# SCH.net
KiCad netlist of a schematic drawn in Altium Designer
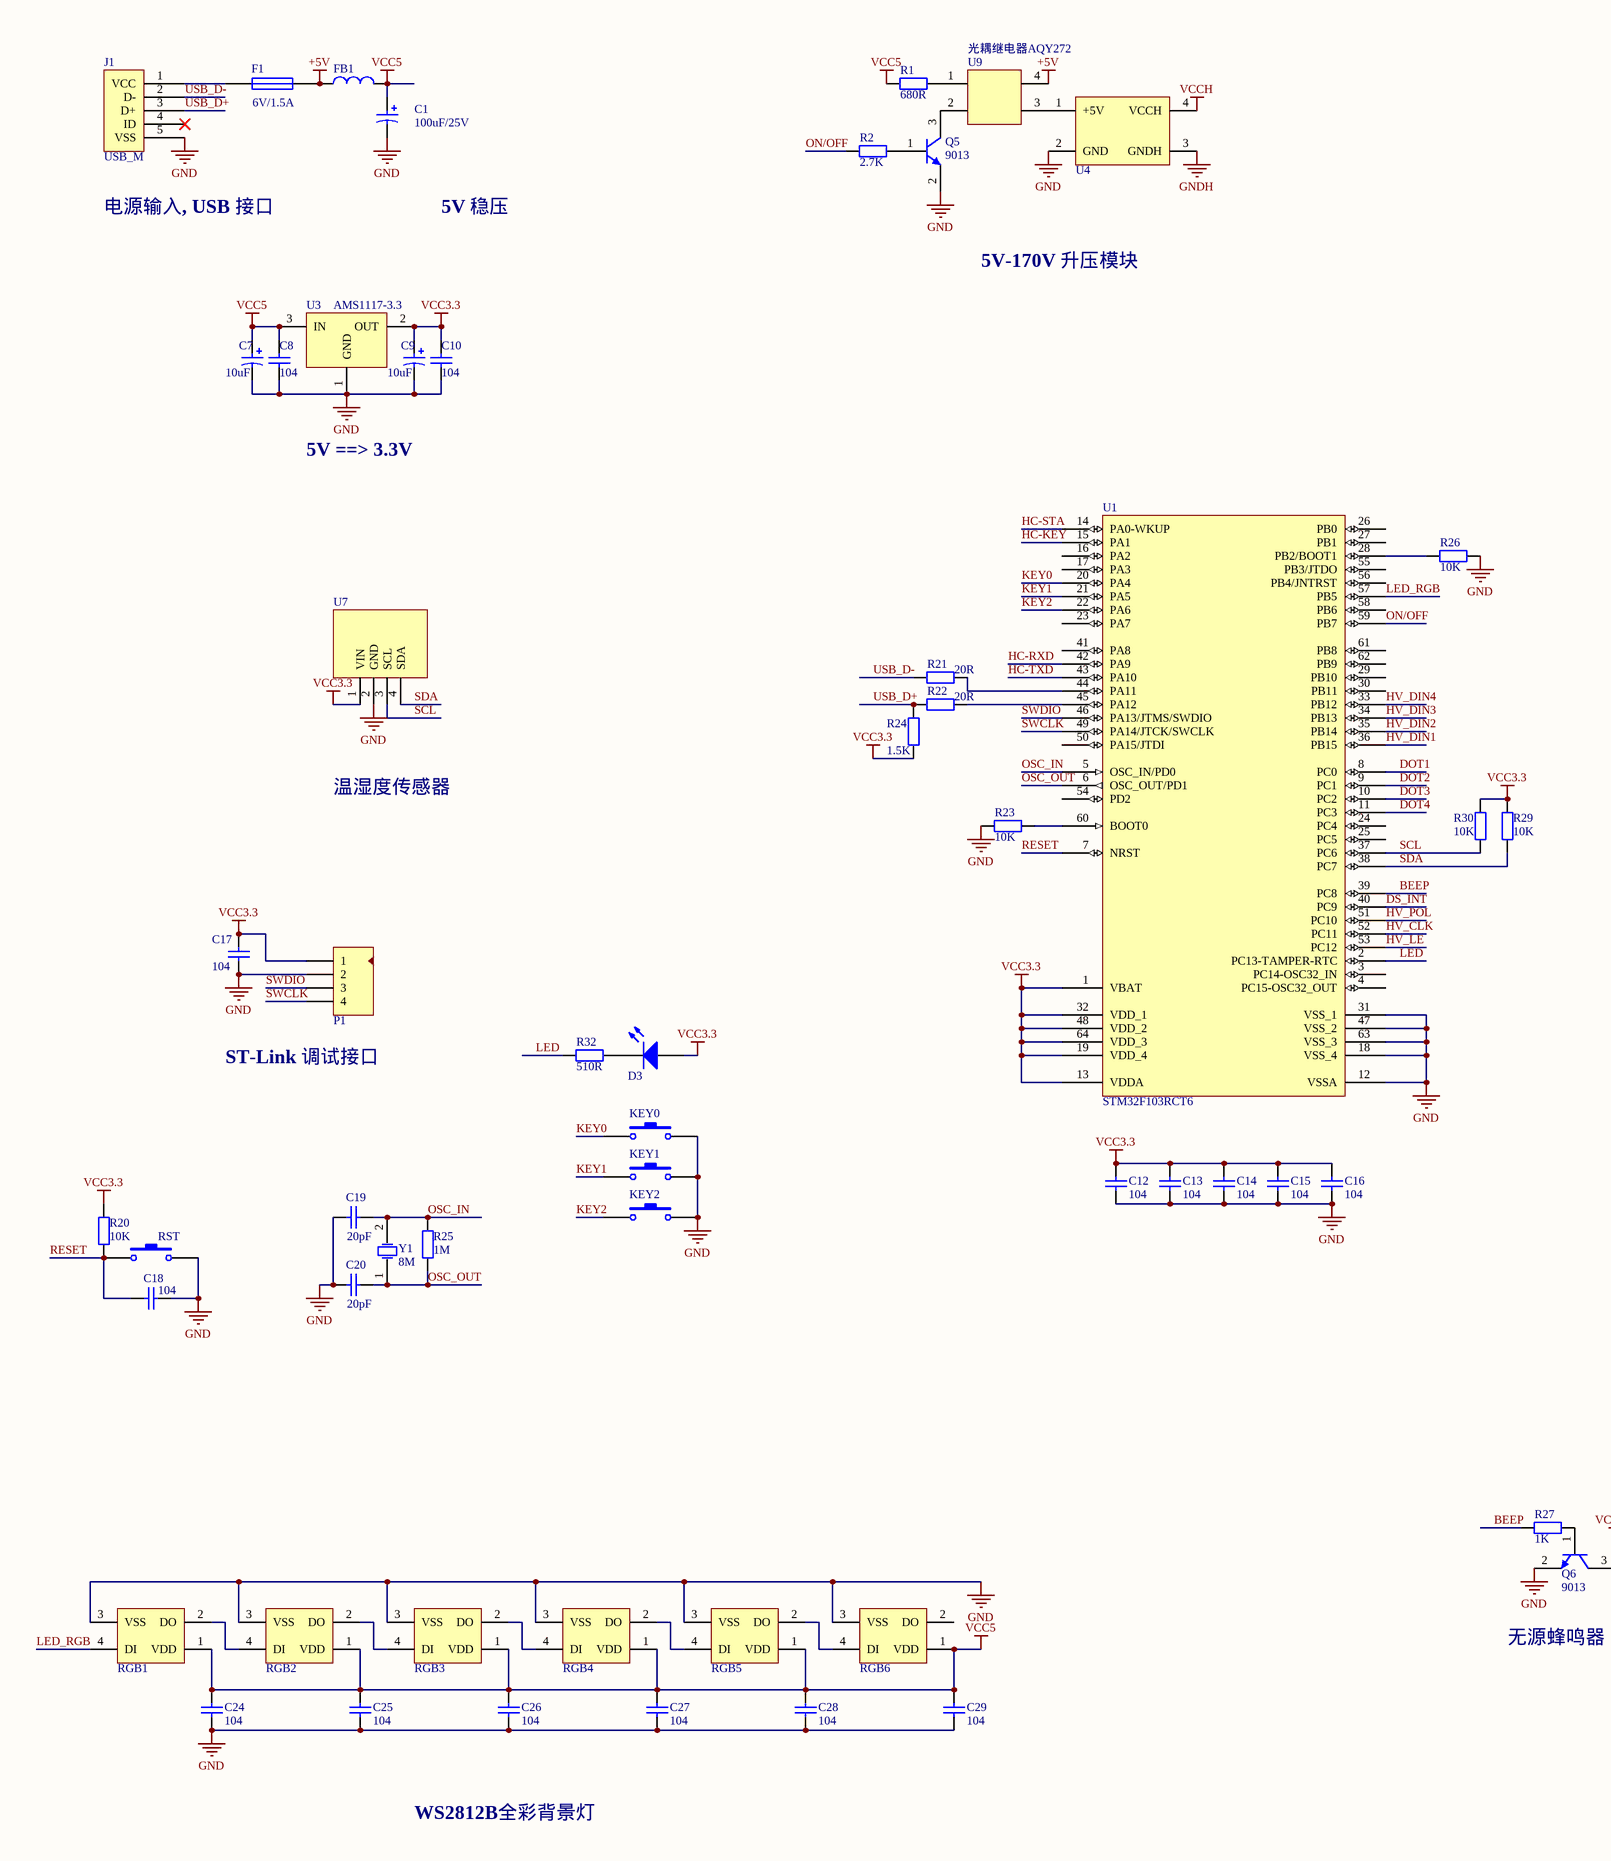
[diagram p0: SCH.SchDoc, left]
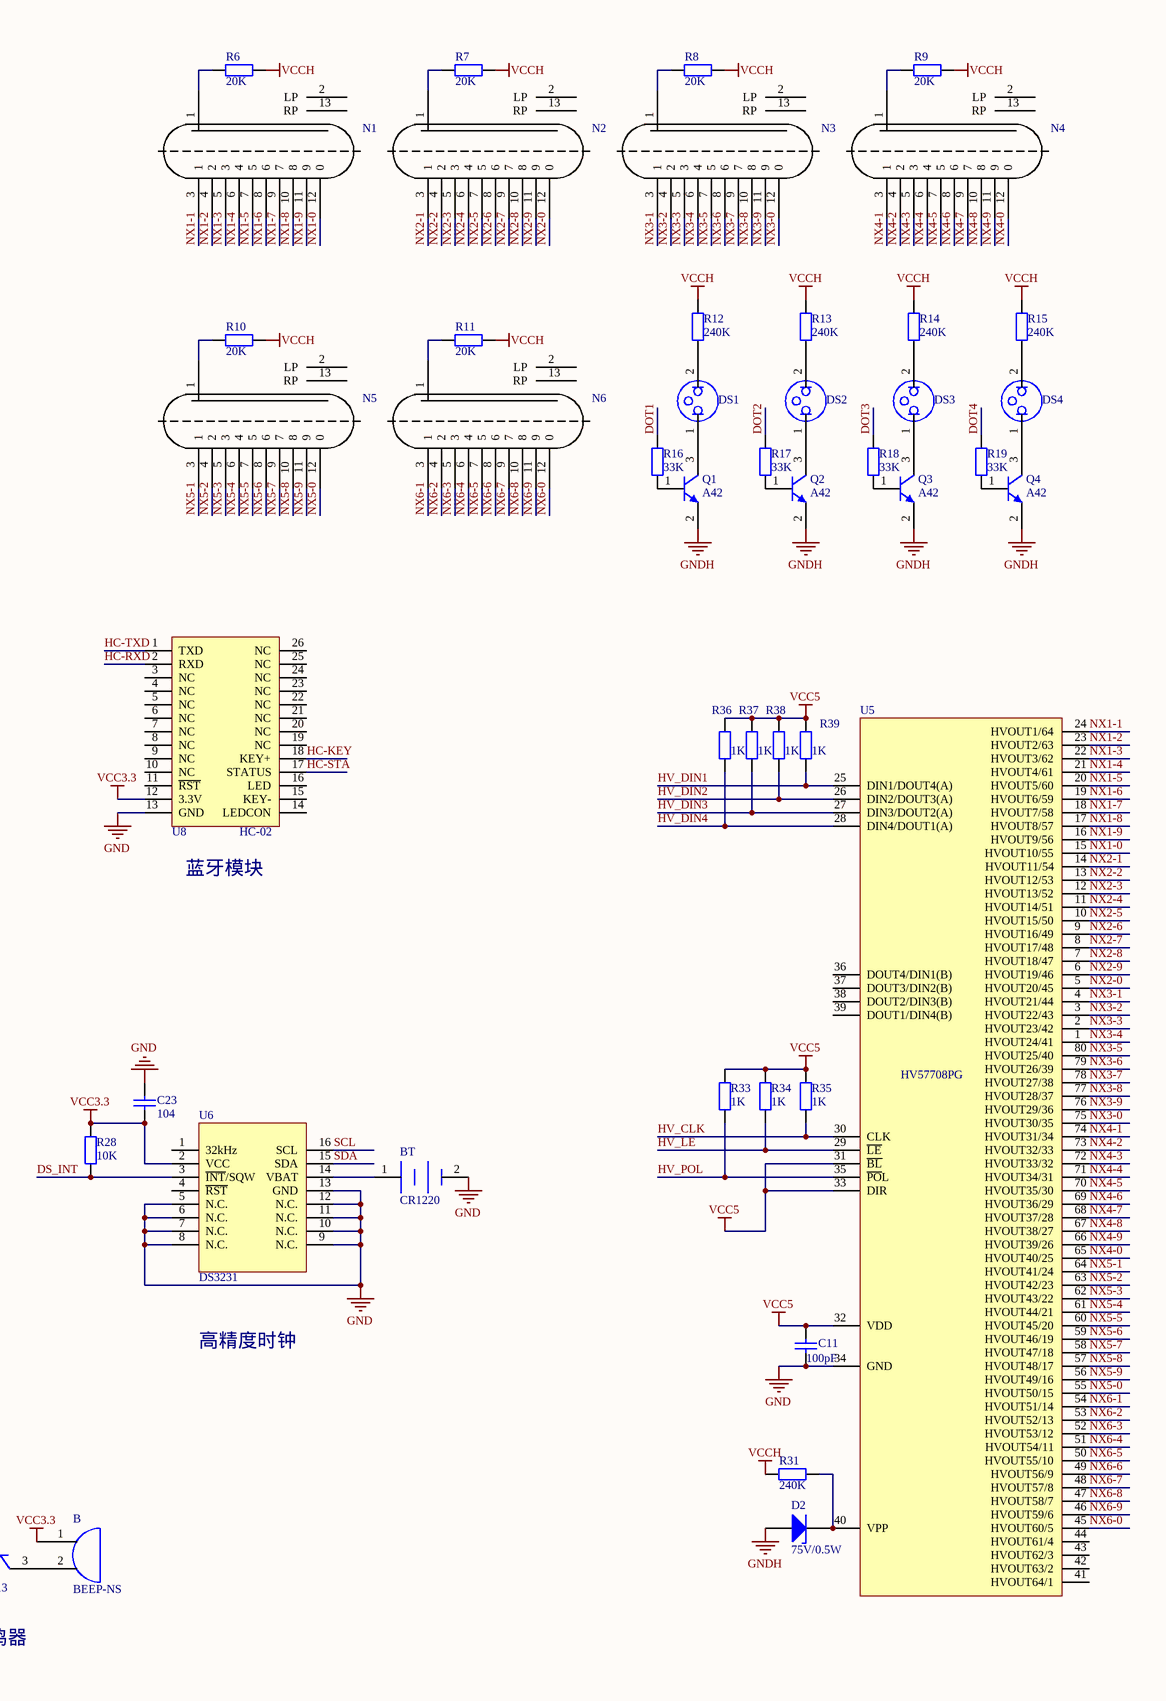
[diagram p1: SCH.SchDoc, right]

(export (version "E")
  (design (tool "Eeschema 10.0.6"))
  (components
    (comp (ref "B")
      (value "BEEP-NS")
      (footprint "BEEP-NS")
      (description "无源蜂鸣器")
      (libsource (lib "ChunLee") (part "BEEP-NS"))
    )
    (comp (ref "BT")
      (value "Battery")
      (footprint "CR1220")
      (fields (field (name "TYPE") "CR1220"))
      (libsource (lib "ChunLee") (part "Battery"))
    )
    (comp (ref "C1")
      (value "100uF/25V")
      (footprint "C-RB-SMD6.3x7.7")
      (description "贴片铝电解电容")
      (fields (field (name "Comment") "Cap-Pol-ES") (field (name "PUBLISHER") "Altium Limited"))
      (libsource (lib "ChunLee") (part "Cap-Pol-ES"))
    )
    (comp (ref "C7")
      (value "10uF")
      (footprint "C-1210")
      (description "钽电容")
      (fields (field (name "Comment") "Cap-Pol") (field (name "PUBLISHER") "Altium Limited"))
      (libsource (lib "ChunLee") (part "Cap-Pol-A"))
    )
    (comp (ref "C8")
      (value "104")
      (footprint "C-0805")
      (description "贴片瓷片电容")
      (fields (field (name "Comment") "Cap-S") (field (name "PUBLISHER") "Altium Limited"))
      (libsource (lib "ChunLee") (part "Cap-S"))
    )
    (comp (ref "C9")
      (value "10uF")
      (footprint "C-1210")
      (description "钽电容")
      (fields (field (name "Comment") "Cap-Pol") (field (name "PUBLISHER") "Altium Limited"))
      (libsource (lib "ChunLee") (part "Cap-Pol-A"))
    )
    (comp (ref "C10")
      (value "104")
      (footprint "C-0805")
      (description "贴片瓷片电容")
      (fields (field (name "Comment") "Cap-S") (field (name "PUBLISHER") "Altium Limited"))
      (libsource (lib "ChunLee") (part "Cap-S"))
    )
    (comp (ref "C11")
      (value "100pF")
      (footprint "C-0805")
      (description "贴片瓷片电容")
      (fields (field (name "Comment") "Cap-S") (field (name "PUBLISHER") "Altium Limited"))
      (libsource (lib "ChunLee") (part "Cap-S"))
    )
    (comp (ref "C12")
      (value "104")
      (footprint "C-0805")
      (description "贴片瓷片电容")
      (fields (field (name "Comment") "Cap-S") (field (name "PUBLISHER") "Altium Limited"))
      (libsource (lib "ChunLee") (part "Cap-S"))
    )
    (comp (ref "C13")
      (value "104")
      (footprint "C-0805")
      (description "贴片瓷片电容")
      (fields (field (name "Comment") "Cap-S") (field (name "PUBLISHER") "Altium Limited"))
      (libsource (lib "ChunLee") (part "Cap-S"))
    )
    (comp (ref "C14")
      (value "104")
      (footprint "C-0805")
      (description "贴片瓷片电容")
      (fields (field (name "Comment") "Cap-S") (field (name "PUBLISHER") "Altium Limited"))
      (libsource (lib "ChunLee") (part "Cap-S"))
    )
    (comp (ref "C15")
      (value "104")
      (footprint "C-0805")
      (description "贴片瓷片电容")
      (fields (field (name "Comment") "Cap-S") (field (name "PUBLISHER") "Altium Limited"))
      (libsource (lib "ChunLee") (part "Cap-S"))
    )
    (comp (ref "C16")
      (value "104")
      (footprint "C-0805")
      (description "贴片瓷片电容")
      (fields (field (name "Comment") "Cap-S") (field (name "PUBLISHER") "Altium Limited"))
      (libsource (lib "ChunLee") (part "Cap-S"))
    )
    (comp (ref "C17")
      (value "104")
      (footprint "C-0805")
      (description "贴片瓷片电容")
      (fields (field (name "Comment") "Cap-S") (field (name "PUBLISHER") "Altium Limited"))
      (libsource (lib "ChunLee") (part "Cap-S"))
    )
    (comp (ref "C18")
      (value "104")
      (footprint "C-0805")
      (description "贴片瓷片电容")
      (fields (field (name "Comment") "Cap-S") (field (name "PUBLISHER") "Altium Limited"))
      (libsource (lib "ChunLee") (part "Cap-S"))
    )
    (comp (ref "C19")
      (value "20pF")
      (footprint "C-0805")
      (description "贴片瓷片电容")
      (fields (field (name "Comment") "Cap-S") (field (name "PUBLISHER") "Altium Limited"))
      (libsource (lib "ChunLee") (part "Cap-S"))
    )
    (comp (ref "C20")
      (value "20pF")
      (footprint "C-0805")
      (description "贴片瓷片电容")
      (fields (field (name "Comment") "Cap-S") (field (name "PUBLISHER") "Altium Limited"))
      (libsource (lib "ChunLee") (part "Cap-S"))
    )
    (comp (ref "C23")
      (value "104")
      (footprint "C-0805")
      (description "贴片瓷片电容")
      (fields (field (name "Comment") "Cap-S") (field (name "PUBLISHER") "Altium Limited"))
      (libsource (lib "ChunLee") (part "Cap-S"))
    )
    (comp (ref "C24")
      (value "104")
      (footprint "C-0805")
      (description "贴片瓷片电容")
      (fields (field (name "Comment") "Cap-S") (field (name "PUBLISHER") "Altium Limited"))
      (libsource (lib "ChunLee") (part "Cap-S"))
    )
    (comp (ref "C25")
      (value "104")
      (footprint "C-0805")
      (description "贴片瓷片电容")
      (fields (field (name "Comment") "Cap-S") (field (name "PUBLISHER") "Altium Limited"))
      (libsource (lib "ChunLee") (part "Cap-S"))
    )
    (comp (ref "C26")
      (value "104")
      (footprint "C-0805")
      (description "贴片瓷片电容")
      (fields (field (name "Comment") "Cap-S") (field (name "PUBLISHER") "Altium Limited"))
      (libsource (lib "ChunLee") (part "Cap-S"))
    )
    (comp (ref "C27")
      (value "104")
      (footprint "C-0805")
      (description "贴片瓷片电容")
      (fields (field (name "Comment") "Cap-S") (field (name "PUBLISHER") "Altium Limited"))
      (libsource (lib "ChunLee") (part "Cap-S"))
    )
    (comp (ref "C28")
      (value "104")
      (footprint "C-0805")
      (description "贴片瓷片电容")
      (fields (field (name "Comment") "Cap-S") (field (name "PUBLISHER") "Altium Limited"))
      (libsource (lib "ChunLee") (part "Cap-S"))
    )
    (comp (ref "C29")
      (value "104")
      (footprint "C-0805")
      (description "贴片瓷片电容")
      (fields (field (name "Comment") "Cap-S") (field (name "PUBLISHER") "Altium Limited"))
      (libsource (lib "ChunLee") (part "Cap-S"))
    )
    (comp (ref "D2")
      (value "75V/0.5W")
      (footprint "D-ll34")
      (description "稳压二极管")
      (fields (field (name "Comment") "ZMM75") (field (name "PUBLISHER") "Altium Limited"))
      (libsource (lib "ChunLee") (part "Diode-Z"))
    )
    (comp (ref "D3")
      (value "LED0")
      (footprint "LED-0805")
      (description "发光二极管")
      (fields (field (name "PUBLISHER") "Altium Limited"))
      (libsource (lib "ChunLee") (part "LED0"))
    )
    (comp (ref "DS1")
      (value "Neon")
      (footprint "PIN2")
      (description "氖泡")
      (libsource (lib "ChunLee") (part "Neon_Lamp"))
    )
    (comp (ref "DS2")
      (value "Neon")
      (footprint "PIN2")
      (description "氖泡")
      (libsource (lib "ChunLee") (part "Neon_Lamp"))
    )
    (comp (ref "DS3")
      (value "Neon")
      (footprint "PIN2")
      (description "氖泡")
      (libsource (lib "ChunLee") (part "Neon_Lamp"))
    )
    (comp (ref "DS4")
      (value "Neon")
      (footprint "PIN2")
      (description "氖泡")
      (libsource (lib "ChunLee") (part "Neon_Lamp"))
    )
    (comp (ref "F1")
      (value "6V/1.5A")
      (footprint "1206")
      (description "保险丝")
      (fields (field (name "Comment") "Fuse1"))
      (libsource (lib "ChunLee") (part "Fuse1"))
    )
    (comp (ref "FB1")
      (value "Inductor")
      (footprint "0805-1")
      (description "磁珠")
      (fields (field (name "PUBLISHER") "Altium Limited"))
      (libsource (lib "ChunLee") (part "Inductor"))
    )
    (comp (ref "J1")
      (value "USB_M")
      (footprint "USB_MICRO")
      (description "Micro/Mini USB")
      (libsource (lib "HDR_ChunLee") (part "USB_M"))
    )
    (comp (ref "KEY0")
      (value "KEY")
      (footprint "SW_PB2_C1")
      (description "微动开关")
      (fields (field (name "PUBLISHER") "Altium Limited"))
      (libsource (lib "ChunLee") (part "SW-PB"))
    )
    (comp (ref "KEY1")
      (value "KEY")
      (footprint "SW_PB2_C1")
      (description "微动开关")
      (fields (field (name "PUBLISHER") "Altium Limited"))
      (libsource (lib "ChunLee") (part "SW-PB"))
    )
    (comp (ref "KEY2")
      (value "KEY")
      (footprint "SW_PB2_C1")
      (description "微动开关")
      (fields (field (name "PUBLISHER") "Altium Limited"))
      (libsource (lib "ChunLee") (part "SW-PB"))
    )
    (comp (ref "N1")
      (value "IN_14")
      (footprint "IN_14")
      (description "辉光管")
      (libsource (lib "ChunLee") (part "IN_14"))
    )
    (comp (ref "N2")
      (value "IN_14")
      (footprint "IN_14")
      (description "辉光管")
      (libsource (lib "ChunLee") (part "IN_14"))
    )
    (comp (ref "N3")
      (value "IN_14")
      (footprint "IN_14")
      (description "辉光管")
      (libsource (lib "ChunLee") (part "IN_14"))
    )
    (comp (ref "N4")
      (value "IN_14")
      (footprint "IN_14")
      (description "辉光管")
      (libsource (lib "ChunLee") (part "IN_14"))
    )
    (comp (ref "N5")
      (value "IN_14")
      (footprint "IN_14")
      (description "辉光管")
      (libsource (lib "ChunLee") (part "IN_14"))
    )
    (comp (ref "N6")
      (value "IN_14")
      (footprint "IN_14")
      (description "辉光管")
      (libsource (lib "ChunLee") (part "IN_14"))
    )
    (comp (ref "P1")
      (value "Header 4")
      (footprint "HDR4X1-2.54")
      (description "接插件")
      (fields (field (name "PUBLISHER") "Altium Limited"))
      (libsource (lib "HDR_ChunLee") (part "Header 4"))
    )
    (comp (ref "Q1")
      (value "A42")
      (footprint "SOT23-3")
      (description "贴片三极管")
      (fields (field (name "PUBLISHER") "Altium Limited"))
      (libsource (lib "ChunLee") (part "NPN1"))
    )
    (comp (ref "Q2")
      (value "A42")
      (footprint "SOT23-3")
      (description "贴片三极管")
      (fields (field (name "PUBLISHER") "Altium Limited"))
      (libsource (lib "ChunLee") (part "NPN1"))
    )
    (comp (ref "Q3")
      (value "A42")
      (footprint "SOT23-3")
      (description "贴片三极管")
      (fields (field (name "PUBLISHER") "Altium Limited"))
      (libsource (lib "ChunLee") (part "NPN1"))
    )
    (comp (ref "Q4")
      (value "A42")
      (footprint "SOT23-3")
      (description "贴片三极管")
      (fields (field (name "PUBLISHER") "Altium Limited"))
      (libsource (lib "ChunLee") (part "NPN1"))
    )
    (comp (ref "Q5")
      (value "9013")
      (footprint "SOT23-3")
      (description "贴片三极管")
      (fields (field (name "PUBLISHER") "Altium Limited"))
      (libsource (lib "ChunLee") (part "NPN1"))
    )
    (comp (ref "Q6")
      (value "9013")
      (footprint "SOT23-3")
      (description "贴片三极管")
      (fields (field (name "PUBLISHER") "Altium Limited"))
      (libsource (lib "ChunLee") (part "NPN1"))
    )
    (comp (ref "R1")
      (value "680R")
      (footprint "0805-1")
      (description "贴片电阻")
      (fields (field (name "Comment") "Res1") (field (name "PUBLISHER") "Altium Limited"))
      (libsource (lib "ChunLee") (part "Res1"))
    )
    (comp (ref "R2")
      (value "2.7K")
      (footprint "0805-1")
      (description "贴片电阻")
      (fields (field (name "Comment") "Res1") (field (name "PUBLISHER") "Altium Limited"))
      (libsource (lib "") (part "Res1_1"))
    )
    (comp (ref "R6")
      (value "20K")
      (footprint "0805-1")
      (description "贴片电阻")
      (fields (field (name "Comment") "Res1") (field (name "PUBLISHER") "Altium Limited"))
      (libsource (lib "ChunLee") (part "Res1"))
    )
    (comp (ref "R7")
      (value "20K")
      (footprint "0805-1")
      (description "贴片电阻")
      (fields (field (name "Comment") "Res1") (field (name "PUBLISHER") "Altium Limited"))
      (libsource (lib "ChunLee") (part "Res1"))
    )
    (comp (ref "R8")
      (value "20K")
      (footprint "0805-1")
      (description "贴片电阻")
      (fields (field (name "Comment") "Res1") (field (name "PUBLISHER") "Altium Limited"))
      (libsource (lib "ChunLee") (part "Res1"))
    )
    (comp (ref "R9")
      (value "20K")
      (footprint "0805-1")
      (description "贴片电阻")
      (fields (field (name "Comment") "Res1") (field (name "PUBLISHER") "Altium Limited"))
      (libsource (lib "ChunLee") (part "Res1"))
    )
    (comp (ref "R10")
      (value "20K")
      (footprint "0805-1")
      (description "贴片电阻")
      (fields (field (name "Comment") "Res1") (field (name "PUBLISHER") "Altium Limited"))
      (libsource (lib "ChunLee") (part "Res1"))
    )
    (comp (ref "R11")
      (value "20K")
      (footprint "0805-1")
      (description "贴片电阻")
      (fields (field (name "Comment") "Res1") (field (name "PUBLISHER") "Altium Limited"))
      (libsource (lib "ChunLee") (part "Res1"))
    )
    (comp (ref "R12")
      (value "240K")
      (footprint "0805-1")
      (description "贴片电阻")
      (fields (field (name "Comment") "Res1") (field (name "PUBLISHER") "Altium Limited"))
      (libsource (lib "") (part "Res1_2"))
    )
    (comp (ref "R13")
      (value "240K")
      (footprint "0805-1")
      (description "贴片电阻")
      (fields (field (name "Comment") "Res1") (field (name "PUBLISHER") "Altium Limited"))
      (libsource (lib "") (part "Res1_2"))
    )
    (comp (ref "R14")
      (value "240K")
      (footprint "0805-1")
      (description "贴片电阻")
      (fields (field (name "Comment") "Res1") (field (name "PUBLISHER") "Altium Limited"))
      (libsource (lib "") (part "Res1_3"))
    )
    (comp (ref "R15")
      (value "240K")
      (footprint "0805-1")
      (description "贴片电阻")
      (fields (field (name "Comment") "Res1") (field (name "PUBLISHER") "Altium Limited"))
      (libsource (lib "") (part "Res1_2"))
    )
    (comp (ref "R16")
      (value "33K")
      (footprint "0805-1")
      (description "贴片电阻")
      (fields (field (name "Comment") "Res1") (field (name "PUBLISHER") "Altium Limited"))
      (libsource (lib "") (part "Res1_2"))
    )
    (comp (ref "R17")
      (value "33K")
      (footprint "0805-1")
      (description "贴片电阻")
      (fields (field (name "Comment") "Res1") (field (name "PUBLISHER") "Altium Limited"))
      (libsource (lib "") (part "Res1_2"))
    )
    (comp (ref "R18")
      (value "33K")
      (footprint "0805-1")
      (description "贴片电阻")
      (fields (field (name "Comment") "Res1") (field (name "PUBLISHER") "Altium Limited"))
      (libsource (lib "") (part "Res1_2"))
    )
    (comp (ref "R19")
      (value "33K")
      (footprint "0805-1")
      (description "贴片电阻")
      (fields (field (name "Comment") "Res1") (field (name "PUBLISHER") "Altium Limited"))
      (libsource (lib "") (part "Res1_2"))
    )
    (comp (ref "R20")
      (value "10K")
      (footprint "0805-1")
      (description "贴片电阻")
      (fields (field (name "Comment") "Res1") (field (name "PUBLISHER") "Altium Limited"))
      (libsource (lib "") (part "Res1_3"))
    )
    (comp (ref "R21")
      (value "20R")
      (footprint "0805-1")
      (description "贴片电阻")
      (fields (field (name "Comment") "Res1") (field (name "PUBLISHER") "Altium Limited"))
      (libsource (lib "ChunLee") (part "Res1"))
    )
    (comp (ref "R22")
      (value "20R")
      (footprint "0805-1")
      (description "贴片电阻")
      (fields (field (name "Comment") "Res1") (field (name "PUBLISHER") "Altium Limited"))
      (libsource (lib "ChunLee") (part "Res1"))
    )
    (comp (ref "R23")
      (value "10K")
      (footprint "0805-1")
      (description "贴片电阻")
      (fields (field (name "Comment") "Res1") (field (name "PUBLISHER") "Altium Limited"))
      (libsource (lib "ChunLee") (part "Res1"))
    )
    (comp (ref "R24")
      (value "1.5K")
      (footprint "0805-1")
      (description "贴片电阻")
      (fields (field (name "Comment") "Res1") (field (name "PUBLISHER") "Altium Limited"))
      (libsource (lib "") (part "Res1_2"))
    )
    (comp (ref "R25")
      (value "1M")
      (footprint "0805-1")
      (description "贴片电阻")
      (fields (field (name "Comment") "Res1") (field (name "PUBLISHER") "Altium Limited"))
      (libsource (lib "") (part "Res1_3"))
    )
    (comp (ref "R26")
      (value "10K")
      (footprint "0805-1")
      (description "贴片电阻")
      (fields (field (name "Comment") "Res1") (field (name "PUBLISHER") "Altium Limited"))
      (libsource (lib "ChunLee") (part "Res1"))
    )
    (comp (ref "R27")
      (value "1K")
      (footprint "0805-1")
      (description "贴片电阻")
      (fields (field (name "Comment") "Res1") (field (name "PUBLISHER") "Altium Limited"))
      (libsource (lib "ChunLee") (part "Res1"))
    )
    (comp (ref "R28")
      (value "10K")
      (footprint "0805-1")
      (description "贴片电阻")
      (fields (field (name "Comment") "Res1") (field (name "PUBLISHER") "Altium Limited"))
      (libsource (lib "") (part "Res1_3"))
    )
    (comp (ref "R29")
      (value "10K")
      (footprint "0805-1")
      (description "贴片电阻")
      (fields (field (name "Comment") "Res1") (field (name "PUBLISHER") "Altium Limited"))
      (libsource (lib "") (part "Res1_3"))
    )
    (comp (ref "R30")
      (value "10K")
      (footprint "0805-1")
      (description "贴片电阻")
      (fields (field (name "Comment") "Res1") (field (name "PUBLISHER") "Altium Limited"))
      (libsource (lib "") (part "Res1_3"))
    )
    (comp (ref "R31")
      (value "240K")
      (footprint "0805-1")
      (description "贴片电阻")
      (fields (field (name "Comment") "Res1") (field (name "PUBLISHER") "Altium Limited"))
      (libsource (lib "ChunLee") (part "Res1"))
    )
    (comp (ref "R32")
      (value "510R")
      (footprint "0805-1")
      (description "贴片电阻")
      (fields (field (name "Comment") "Res1") (field (name "PUBLISHER") "Altium Limited"))
      (libsource (lib "ChunLee") (part "Res1"))
    )
    (comp (ref "R33")
      (value "1K")
      (footprint "0805-1")
      (description "贴片电阻")
      (fields (field (name "Comment") "Res1") (field (name "PUBLISHER") "Altium Limited"))
      (libsource (lib "") (part "Res1_3"))
    )
    (comp (ref "R34")
      (value "1K")
      (footprint "0805-1")
      (description "贴片电阻")
      (fields (field (name "Comment") "Res1") (field (name "PUBLISHER") "Altium Limited"))
      (libsource (lib "") (part "Res1_3"))
    )
    (comp (ref "R35")
      (value "1K")
      (footprint "0805-1")
      (description "贴片电阻")
      (fields (field (name "Comment") "Res1") (field (name "PUBLISHER") "Altium Limited"))
      (libsource (lib "") (part "Res1_3"))
    )
    (comp (ref "R36")
      (value "1K")
      (footprint "0805-1")
      (description "贴片电阻")
      (fields (field (name "Comment") "Res1") (field (name "PUBLISHER") "Altium Limited"))
      (libsource (lib "") (part "Res1_3"))
    )
    (comp (ref "R37")
      (value "1K")
      (footprint "0805-1")
      (description "贴片电阻")
      (fields (field (name "Comment") "Res1") (field (name "PUBLISHER") "Altium Limited"))
      (libsource (lib "") (part "Res1_3"))
    )
    (comp (ref "R38")
      (value "1K")
      (footprint "0805-1")
      (description "贴片电阻")
      (fields (field (name "Comment") "Res1") (field (name "PUBLISHER") "Altium Limited"))
      (libsource (lib "") (part "Res1_3"))
    )
    (comp (ref "R39")
      (value "1K")
      (footprint "0805-1")
      (description "贴片电阻")
      (fields (field (name "Comment") "Res1") (field (name "PUBLISHER") "Altium Limited"))
      (libsource (lib "") (part "Res1_3"))
    )
    (comp (ref "RGB1")
      (value "WS2812B")
      (footprint "SMD-5050-4")
      (description "WS2812B 4脚RGB全彩LED")
      (libsource (lib "ChunLee") (part "WS2812B"))
    )
    (comp (ref "RGB2")
      (value "WS2812B")
      (footprint "SMD-5050-4")
      (description "WS2812B 4脚RGB全彩LED")
      (libsource (lib "ChunLee") (part "WS2812B"))
    )
    (comp (ref "RGB3")
      (value "WS2812B")
      (footprint "SMD-5050-4")
      (description "WS2812B 4脚RGB全彩LED")
      (libsource (lib "ChunLee") (part "WS2812B"))
    )
    (comp (ref "RGB4")
      (value "WS2812B")
      (footprint "SMD-5050-4")
      (description "WS2812B 4脚RGB全彩LED")
      (libsource (lib "ChunLee") (part "WS2812B"))
    )
    (comp (ref "RGB5")
      (value "WS2812B")
      (footprint "SMD-5050-4")
      (description "WS2812B 4脚RGB全彩LED")
      (libsource (lib "ChunLee") (part "WS2812B"))
    )
    (comp (ref "RGB6")
      (value "WS2812B")
      (footprint "SMD-5050-4")
      (description "WS2812B 4脚RGB全彩LED")
      (libsource (lib "ChunLee") (part "WS2812B"))
    )
    (comp (ref "RST")
      (value "SW-PB")
      (footprint "SW_PB2_A1")
      (description "微动开关")
      (fields (field (name "PUBLISHER") "Altium Limited"))
      (libsource (lib "ChunLee") (part "SW-PB"))
    )
    (comp (ref "U1")
      (value "STM32F103RCT6")
      (footprint "LQFP-64")
      (description "STM32F103, 64引脚, 256Kb Flash, 48Kb SRAM")
      (fields (field (name "PUBLISHER") "Altium Limited"))
      (libsource (lib "ChunLee") (part "STM32F103RCT6"))
    )
    (comp (ref "U3")
      (value "AMS1117-3.3")
      (footprint "SOT223")
      (description "3.3V稳压芯片")
      (libsource (lib "ChunLee") (part "AMS1117"))
    )
    (comp (ref "U4")
      (value "Boost")
      (footprint "BOOST-A")
      (description "5V-->170V")
      (libsource (lib "Nixie_Schlib") (part "升压模块5V-170V"))
    )
    (comp (ref "U5")
      (value "HV57708PG")
      (footprint "PQFP-80")
      (description "32MHz, 64通道推挽输出串入并出芯片")
      (libsource (lib "ChunLee") (part "HV57708PG"))
    )
    (comp (ref "U6")
      (value "DS3231")
      (footprint "SOIC-16W")
      (description "高精度时钟芯片")
      (libsource (lib "ChunLee") (part "DS3231"))
    )
    (comp (ref "U7")
      (value "SHT30")
      (footprint "SHT30")
      (description "温湿度传感器模块")
      (libsource (lib "ChunLee") (part "SHT30"))
    )
    (comp (ref "U8")
      (value "HC-02")
      (footprint "HC-02")
      (description "串口蓝牙4.0, 10m")
      (libsource (lib "ChunLee") (part "HC-02"))
    )
    (comp (ref "U9")
      (value "光耦继电器AQY272")
      (footprint "AQY272-SOP")
      (description "继电器")
      (libsource (lib "ChunLee") (part "RELAY-AQY272"))
    )
    (comp (ref "Y1")
      (value "8M")
      (footprint "X-SM49")
      (description "晶振")
      (fields (field (name "Comment") "XTAL") (field (name "PUBLISHER") "Altium Limited"))
      (libsource (lib "ChunLee") (part "XTAL"))
    )
  )
  (nets
    (net (code "1") (name "+5V") (class "Default")
      (node (ref "F1") (pin "2") (pinfunction "2_2") (pintype "passive"))
      (node (ref "FB1") (pin "1") (pinfunction "1_1") (pintype "passive"))
      (node (ref "U9") (pin "4") (pinfunction "4_4") (pintype "passive"))
    )
    (net (code "2") (name "/BEEP") (class "Default")
      (node (ref "R27") (pin "1") (pinfunction "1_1") (pintype "passive"))
      (node (ref "U1") (pin "39") (pinfunction "PC8_39") (pintype "bidirectional"))
    )
    (net (code "3") (name "/DOT1") (class "Default")
      (node (ref "R16") (pin "1") (pinfunction "1_1") (pintype "passive"))
      (node (ref "U1") (pin "8") (pinfunction "PC0_8") (pintype "bidirectional"))
    )
    (net (code "4") (name "/DOT2") (class "Default")
      (node (ref "R17") (pin "1") (pinfunction "1_1") (pintype "passive"))
      (node (ref "U1") (pin "9") (pinfunction "PC1_9") (pintype "bidirectional"))
    )
    (net (code "5") (name "/DOT3") (class "Default")
      (node (ref "R18") (pin "1") (pinfunction "1_1") (pintype "passive"))
      (node (ref "U1") (pin "10") (pinfunction "PC2_10") (pintype "bidirectional"))
    )
    (net (code "6") (name "/DOT4") (class "Default")
      (node (ref "R19") (pin "1") (pinfunction "1_1") (pintype "passive"))
      (node (ref "U1") (pin "11") (pinfunction "PC3_11") (pintype "bidirectional"))
    )
    (net (code "7") (name "/DS_INT") (class "Default")
      (node (ref "R28") (pin "1") (pinfunction "1_1") (pintype "passive"))
      (node (ref "U1") (pin "40") (pinfunction "PC9_40") (pintype "bidirectional"))
      (node (ref "U6") (pin "3") (pinfunction "~{INT}/SQW_3") (pintype "passive"))
    )
    (net (code "8") (name "/HC-KEY") (class "Default")
      (node (ref "U1") (pin "15") (pinfunction "PA1_15") (pintype "bidirectional"))
      (node (ref "U8") (pin "18") (pinfunction "KEY+_18") (pintype "passive"))
    )
    (net (code "9") (name "/HC-RXD") (class "Default")
      (node (ref "U1") (pin "42") (pinfunction "PA9_42") (pintype "bidirectional"))
      (node (ref "U8") (pin "2") (pinfunction "RXD_2") (pintype "passive"))
    )
    (net (code "10") (name "/HC-STA") (class "Default")
      (node (ref "U1") (pin "14") (pinfunction "PA0-WKUP_14") (pintype "bidirectional"))
      (node (ref "U8") (pin "17") (pinfunction "STATUS_17") (pintype "passive"))
    )
    (net (code "11") (name "/HC-TXD") (class "Default")
      (node (ref "U1") (pin "43") (pinfunction "PA10_43") (pintype "bidirectional"))
      (node (ref "U8") (pin "1") (pinfunction "TXD_1") (pintype "passive"))
    )
    (net (code "12") (name "/HV_CLK") (class "Default")
      (node (ref "R35") (pin "1") (pinfunction "1_1") (pintype "passive"))
      (node (ref "U1") (pin "52") (pinfunction "PC11_52") (pintype "bidirectional"))
      (node (ref "U5") (pin "30") (pinfunction "CLK_30") (pintype "passive"))
    )
    (net (code "13") (name "/HV_DIN1") (class "Default")
      (node (ref "R39") (pin "1") (pinfunction "1_1") (pintype "passive"))
      (node (ref "U1") (pin "36") (pinfunction "PB15_36") (pintype "bidirectional"))
      (node (ref "U5") (pin "25") (pinfunction "DIN1/DOUT4(A)_25") (pintype "passive"))
    )
    (net (code "14") (name "/HV_DIN2") (class "Default")
      (node (ref "R38") (pin "1") (pinfunction "1_1") (pintype "passive"))
      (node (ref "U1") (pin "35") (pinfunction "PB14_35") (pintype "bidirectional"))
      (node (ref "U5") (pin "26") (pinfunction "DIN2/DOUT3(A)_26") (pintype "passive"))
    )
    (net (code "15") (name "/HV_DIN3") (class "Default")
      (node (ref "R37") (pin "1") (pinfunction "1_1") (pintype "passive"))
      (node (ref "U1") (pin "34") (pinfunction "PB13_34") (pintype "bidirectional"))
      (node (ref "U5") (pin "27") (pinfunction "DIN3/DOUT2(A)_27") (pintype "passive"))
    )
    (net (code "16") (name "/HV_DIN4") (class "Default")
      (node (ref "R36") (pin "1") (pinfunction "1_1") (pintype "passive"))
      (node (ref "U1") (pin "33") (pinfunction "PB12_33") (pintype "bidirectional"))
      (node (ref "U5") (pin "28") (pinfunction "DIN4/DOUT1(A)_28") (pintype "passive"))
    )
    (net (code "17") (name "/HV_LE") (class "Default")
      (node (ref "R34") (pin "1") (pinfunction "1_1") (pintype "passive"))
      (node (ref "U1") (pin "53") (pinfunction "PC12_53") (pintype "bidirectional"))
      (node (ref "U5") (pin "29") (pinfunction "~{LE}_29") (pintype "passive"))
    )
    (net (code "18") (name "/HV_POL") (class "Default")
      (node (ref "R33") (pin "1") (pinfunction "1_1") (pintype "passive"))
      (node (ref "U1") (pin "51") (pinfunction "PC10_51") (pintype "bidirectional"))
      (node (ref "U5") (pin "35") (pinfunction "~{PO}L_35") (pintype "passive"))
    )
    (net (code "19") (name "/KEY0") (class "Default")
      (node (ref "KEY0") (pin "1") (pinfunction "1_1") (pintype "passive"))
      (node (ref "U1") (pin "20") (pinfunction "PA4_20") (pintype "bidirectional"))
    )
    (net (code "20") (name "/KEY1") (class "Default")
      (node (ref "KEY1") (pin "1") (pinfunction "1_1") (pintype "passive"))
      (node (ref "U1") (pin "21") (pinfunction "PA5_21") (pintype "bidirectional"))
    )
    (net (code "21") (name "/KEY2") (class "Default")
      (node (ref "KEY2") (pin "1") (pinfunction "1_1") (pintype "passive"))
      (node (ref "U1") (pin "22") (pinfunction "PA6_22") (pintype "bidirectional"))
    )
    (net (code "22") (name "/LED") (class "Default")
      (node (ref "R32") (pin "1") (pinfunction "1_1") (pintype "passive"))
      (node (ref "U1") (pin "2") (pinfunction "PC13-TAMPER-RTC_2") (pintype "bidirectional"))
    )
    (net (code "23") (name "/LED_RGB") (class "Default")
      (node (ref "RGB1") (pin "4") (pinfunction "DI_4") (pintype "passive"))
      (node (ref "U1") (pin "57") (pinfunction "PB5_57") (pintype "bidirectional"))
    )
    (net (code "24") (name "/NX1-0") (class "Default")
      (node (ref "N1") (pin "12") (pinfunction "0_12") (pintype "passive"))
      (node (ref "U5") (pin "15") (pinfunction "HVOUT10/55_15") (pintype "passive"))
    )
    (net (code "25") (name "/NX1-1") (class "Default")
      (node (ref "N1") (pin "3") (pinfunction "1_3") (pintype "passive"))
      (node (ref "U5") (pin "24") (pinfunction "HVOUT1/64_24") (pintype "passive"))
    )
    (net (code "26") (name "/NX1-2") (class "Default")
      (node (ref "N1") (pin "4") (pinfunction "2_4") (pintype "passive"))
      (node (ref "U5") (pin "23") (pinfunction "HVOUT2/63_23") (pintype "passive"))
    )
    (net (code "27") (name "/NX1-3") (class "Default")
      (node (ref "N1") (pin "5") (pinfunction "3_5") (pintype "passive"))
      (node (ref "U5") (pin "22") (pinfunction "HVOUT3/62_22") (pintype "passive"))
    )
    (net (code "28") (name "/NX1-4") (class "Default")
      (node (ref "N1") (pin "6") (pinfunction "4_6") (pintype "passive"))
      (node (ref "U5") (pin "21") (pinfunction "HVOUT4/61_21") (pintype "passive"))
    )
    (net (code "29") (name "/NX1-5") (class "Default")
      (node (ref "N1") (pin "7") (pinfunction "5_7") (pintype "passive"))
      (node (ref "U5") (pin "20") (pinfunction "HVOUT5/60_20") (pintype "passive"))
    )
    (net (code "30") (name "/NX1-6") (class "Default")
      (node (ref "N1") (pin "8") (pinfunction "6_8") (pintype "passive"))
      (node (ref "U5") (pin "19") (pinfunction "HVOUT6/59_19") (pintype "passive"))
    )
    (net (code "31") (name "/NX1-7") (class "Default")
      (node (ref "N1") (pin "9") (pinfunction "7_9") (pintype "passive"))
      (node (ref "U5") (pin "18") (pinfunction "HVOUT7/58_18") (pintype "passive"))
    )
    (net (code "32") (name "/NX1-8") (class "Default")
      (node (ref "N1") (pin "10") (pinfunction "8_10") (pintype "passive"))
      (node (ref "U5") (pin "17") (pinfunction "HVOUT8/57_17") (pintype "passive"))
    )
    (net (code "33") (name "/NX1-9") (class "Default")
      (node (ref "N1") (pin "11") (pinfunction "9_11") (pintype "passive"))
      (node (ref "U5") (pin "16") (pinfunction "HVOUT9/56_16") (pintype "passive"))
    )
    (net (code "34") (name "/NX2-0") (class "Default")
      (node (ref "N2") (pin "12") (pinfunction "0_12") (pintype "passive"))
      (node (ref "U5") (pin "5") (pinfunction "HVOUT20/45_5") (pintype "passive"))
    )
    (net (code "35") (name "/NX2-1") (class "Default")
      (node (ref "N2") (pin "3") (pinfunction "1_3") (pintype "passive"))
      (node (ref "U5") (pin "14") (pinfunction "HVOUT11/54_14") (pintype "passive"))
    )
    (net (code "36") (name "/NX2-2") (class "Default")
      (node (ref "N2") (pin "4") (pinfunction "2_4") (pintype "passive"))
      (node (ref "U5") (pin "13") (pinfunction "HVOUT12/53_13") (pintype "passive"))
    )
    (net (code "37") (name "/NX2-3") (class "Default")
      (node (ref "N2") (pin "5") (pinfunction "3_5") (pintype "passive"))
      (node (ref "U5") (pin "12") (pinfunction "HVOUT13/52_12") (pintype "passive"))
    )
    (net (code "38") (name "/NX2-4") (class "Default")
      (node (ref "N2") (pin "6") (pinfunction "4_6") (pintype "passive"))
      (node (ref "U5") (pin "11") (pinfunction "HVOUT14/51_11") (pintype "passive"))
    )
    (net (code "39") (name "/NX2-5") (class "Default")
      (node (ref "N2") (pin "7") (pinfunction "5_7") (pintype "passive"))
      (node (ref "U5") (pin "10") (pinfunction "HVOUT15/50_10") (pintype "passive"))
    )
    (net (code "40") (name "/NX2-6") (class "Default")
      (node (ref "N2") (pin "8") (pinfunction "6_8") (pintype "passive"))
      (node (ref "U5") (pin "9") (pinfunction "HVOUT16/49_9") (pintype "passive"))
    )
    (net (code "41") (name "/NX2-7") (class "Default")
      (node (ref "N2") (pin "9") (pinfunction "7_9") (pintype "passive"))
      (node (ref "U5") (pin "8") (pinfunction "HVOUT17/48_8") (pintype "passive"))
    )
    (net (code "42") (name "/NX2-8") (class "Default")
      (node (ref "N2") (pin "10") (pinfunction "8_10") (pintype "passive"))
      (node (ref "U5") (pin "7") (pinfunction "HVOUT18/47_7") (pintype "passive"))
    )
    (net (code "43") (name "/NX2-9") (class "Default")
      (node (ref "N2") (pin "11") (pinfunction "9_11") (pintype "passive"))
      (node (ref "U5") (pin "6") (pinfunction "HVOUT19/46_6") (pintype "passive"))
    )
    (net (code "44") (name "/NX3-0") (class "Default")
      (node (ref "N3") (pin "12") (pinfunction "0_12") (pintype "passive"))
      (node (ref "U5") (pin "75") (pinfunction "HVOUT30/35_75") (pintype "passive"))
    )
    (net (code "45") (name "/NX3-1") (class "Default")
      (node (ref "N3") (pin "3") (pinfunction "1_3") (pintype "passive"))
      (node (ref "U5") (pin "4") (pinfunction "HVOUT21/44_4") (pintype "passive"))
    )
    (net (code "46") (name "/NX3-2") (class "Default")
      (node (ref "N3") (pin "4") (pinfunction "2_4") (pintype "passive"))
      (node (ref "U5") (pin "3") (pinfunction "HVOUT22/43_3") (pintype "passive"))
    )
    (net (code "47") (name "/NX3-3") (class "Default")
      (node (ref "N3") (pin "5") (pinfunction "3_5") (pintype "passive"))
      (node (ref "U5") (pin "2") (pinfunction "HVOUT23/42_2") (pintype "passive"))
    )
    (net (code "48") (name "/NX3-4") (class "Default")
      (node (ref "N3") (pin "6") (pinfunction "4_6") (pintype "passive"))
      (node (ref "U5") (pin "1") (pinfunction "HVOUT24/41_1") (pintype "passive"))
    )
    (net (code "49") (name "/NX3-5") (class "Default")
      (node (ref "N3") (pin "7") (pinfunction "5_7") (pintype "passive"))
      (node (ref "U5") (pin "80") (pinfunction "HVOUT25/40_80") (pintype "passive"))
    )
    (net (code "50") (name "/NX3-6") (class "Default")
      (node (ref "N3") (pin "8") (pinfunction "6_8") (pintype "passive"))
      (node (ref "U5") (pin "79") (pinfunction "HVOUT26/39_79") (pintype "passive"))
    )
    (net (code "51") (name "/NX3-7") (class "Default")
      (node (ref "N3") (pin "9") (pinfunction "7_9") (pintype "passive"))
      (node (ref "U5") (pin "78") (pinfunction "HVOUT27/38_78") (pintype "passive"))
    )
    (net (code "52") (name "/NX3-8") (class "Default")
      (node (ref "N3") (pin "10") (pinfunction "8_10") (pintype "passive"))
      (node (ref "U5") (pin "77") (pinfunction "HVOUT28/37_77") (pintype "passive"))
    )
    (net (code "53") (name "/NX3-9") (class "Default")
      (node (ref "N3") (pin "11") (pinfunction "9_11") (pintype "passive"))
      (node (ref "U5") (pin "76") (pinfunction "HVOUT29/36_76") (pintype "passive"))
    )
    (net (code "54") (name "/NX4-0") (class "Default")
      (node (ref "N4") (pin "12") (pinfunction "0_12") (pintype "passive"))
      (node (ref "U5") (pin "65") (pinfunction "HVOUT40/25_65") (pintype "passive"))
    )
    (net (code "55") (name "/NX4-1") (class "Default")
      (node (ref "N4") (pin "3") (pinfunction "1_3") (pintype "passive"))
      (node (ref "U5") (pin "74") (pinfunction "HVOUT31/34_74") (pintype "passive"))
    )
    (net (code "56") (name "/NX4-2") (class "Default")
      (node (ref "N4") (pin "4") (pinfunction "2_4") (pintype "passive"))
      (node (ref "U5") (pin "73") (pinfunction "HVOUT32/33_73") (pintype "passive"))
    )
    (net (code "57") (name "/NX4-3") (class "Default")
      (node (ref "N4") (pin "5") (pinfunction "3_5") (pintype "passive"))
      (node (ref "U5") (pin "72") (pinfunction "HVOUT33/32_72") (pintype "passive"))
    )
    (net (code "58") (name "/NX4-4") (class "Default")
      (node (ref "N4") (pin "6") (pinfunction "4_6") (pintype "passive"))
      (node (ref "U5") (pin "71") (pinfunction "HVOUT34/31_71") (pintype "passive"))
    )
    (net (code "59") (name "/NX4-5") (class "Default")
      (node (ref "N4") (pin "7") (pinfunction "5_7") (pintype "passive"))
      (node (ref "U5") (pin "70") (pinfunction "HVOUT35/30_70") (pintype "passive"))
    )
    (net (code "60") (name "/NX4-6") (class "Default")
      (node (ref "N4") (pin "8") (pinfunction "6_8") (pintype "passive"))
      (node (ref "U5") (pin "69") (pinfunction "HVOUT36/29_69") (pintype "passive"))
    )
    (net (code "61") (name "/NX4-7") (class "Default")
      (node (ref "N4") (pin "9") (pinfunction "7_9") (pintype "passive"))
      (node (ref "U5") (pin "68") (pinfunction "HVOUT37/28_68") (pintype "passive"))
    )
    (net (code "62") (name "/NX4-8") (class "Default")
      (node (ref "N4") (pin "10") (pinfunction "8_10") (pintype "passive"))
      (node (ref "U5") (pin "67") (pinfunction "HVOUT38/27_67") (pintype "passive"))
    )
    (net (code "63") (name "/NX4-9") (class "Default")
      (node (ref "N4") (pin "11") (pinfunction "9_11") (pintype "passive"))
      (node (ref "U5") (pin "66") (pinfunction "HVOUT39/26_66") (pintype "passive"))
    )
    (net (code "64") (name "/NX5-0") (class "Default")
      (node (ref "N5") (pin "12") (pinfunction "0_12") (pintype "passive"))
      (node (ref "U5") (pin "55") (pinfunction "HVOUT50/15_55") (pintype "passive"))
    )
    (net (code "65") (name "/NX5-1") (class "Default")
      (node (ref "N5") (pin "3") (pinfunction "1_3") (pintype "passive"))
      (node (ref "U5") (pin "64") (pinfunction "HVOUT41/24_64") (pintype "passive"))
    )
    (net (code "66") (name "/NX5-2") (class "Default")
      (node (ref "N5") (pin "4") (pinfunction "2_4") (pintype "passive"))
      (node (ref "U5") (pin "63") (pinfunction "HVOUT42/23_63") (pintype "passive"))
    )
    (net (code "67") (name "/NX5-3") (class "Default")
      (node (ref "N5") (pin "5") (pinfunction "3_5") (pintype "passive"))
      (node (ref "U5") (pin "62") (pinfunction "HVOUT43/22_62") (pintype "passive"))
    )
    (net (code "68") (name "/NX5-4") (class "Default")
      (node (ref "N5") (pin "6") (pinfunction "4_6") (pintype "passive"))
      (node (ref "U5") (pin "61") (pinfunction "HVOUT44/21_61") (pintype "passive"))
    )
    (net (code "69") (name "/NX5-5") (class "Default")
      (node (ref "N5") (pin "7") (pinfunction "5_7") (pintype "passive"))
      (node (ref "U5") (pin "60") (pinfunction "HVOUT45/20_60") (pintype "passive"))
    )
    (net (code "70") (name "/NX5-6") (class "Default")
      (node (ref "N5") (pin "8") (pinfunction "6_8") (pintype "passive"))
      (node (ref "U5") (pin "59") (pinfunction "HVOUT46/19_59") (pintype "passive"))
    )
    (net (code "71") (name "/NX5-7") (class "Default")
      (node (ref "N5") (pin "9") (pinfunction "7_9") (pintype "passive"))
      (node (ref "U5") (pin "58") (pinfunction "HVOUT47/18_58") (pintype "passive"))
    )
    (net (code "72") (name "/NX5-8") (class "Default")
      (node (ref "N5") (pin "10") (pinfunction "8_10") (pintype "passive"))
      (node (ref "U5") (pin "57") (pinfunction "HVOUT48/17_57") (pintype "passive"))
    )
    (net (code "73") (name "/NX5-9") (class "Default")
      (node (ref "N5") (pin "11") (pinfunction "9_11") (pintype "passive"))
      (node (ref "U5") (pin "56") (pinfunction "HVOUT49/16_56") (pintype "passive"))
    )
    (net (code "74") (name "/NX6-0") (class "Default")
      (node (ref "N6") (pin "12") (pinfunction "0_12") (pintype "passive"))
      (node (ref "U5") (pin "45") (pinfunction "HVOUT60/5_45") (pintype "passive"))
    )
    (net (code "75") (name "/NX6-1") (class "Default")
      (node (ref "N6") (pin "3") (pinfunction "1_3") (pintype "passive"))
      (node (ref "U5") (pin "54") (pinfunction "HVOUT51/14_54") (pintype "passive"))
    )
    (net (code "76") (name "/NX6-2") (class "Default")
      (node (ref "N6") (pin "4") (pinfunction "2_4") (pintype "passive"))
      (node (ref "U5") (pin "53") (pinfunction "HVOUT52/13_53") (pintype "passive"))
    )
    (net (code "77") (name "/NX6-3") (class "Default")
      (node (ref "N6") (pin "5") (pinfunction "3_5") (pintype "passive"))
      (node (ref "U5") (pin "52") (pinfunction "HVOUT53/12_52") (pintype "passive"))
    )
    (net (code "78") (name "/NX6-4") (class "Default")
      (node (ref "N6") (pin "6") (pinfunction "4_6") (pintype "passive"))
      (node (ref "U5") (pin "51") (pinfunction "HVOUT54/11_51") (pintype "passive"))
    )
    (net (code "79") (name "/NX6-5") (class "Default")
      (node (ref "N6") (pin "7") (pinfunction "5_7") (pintype "passive"))
      (node (ref "U5") (pin "50") (pinfunction "HVOUT55/10_50") (pintype "passive"))
    )
    (net (code "80") (name "/NX6-6") (class "Default")
      (node (ref "N6") (pin "8") (pinfunction "6_8") (pintype "passive"))
      (node (ref "U5") (pin "49") (pinfunction "HVOUT56/9_49") (pintype "passive"))
    )
    (net (code "81") (name "/NX6-7") (class "Default")
      (node (ref "N6") (pin "9") (pinfunction "7_9") (pintype "passive"))
      (node (ref "U5") (pin "48") (pinfunction "HVOUT57/8_48") (pintype "passive"))
    )
    (net (code "82") (name "/NX6-8") (class "Default")
      (node (ref "N6") (pin "10") (pinfunction "8_10") (pintype "passive"))
      (node (ref "U5") (pin "47") (pinfunction "HVOUT58/7_47") (pintype "passive"))
    )
    (net (code "83") (name "/NX6-9") (class "Default")
      (node (ref "N6") (pin "11") (pinfunction "9_11") (pintype "passive"))
      (node (ref "U5") (pin "46") (pinfunction "HVOUT59/6_46") (pintype "passive"))
    )
    (net (code "84") (name "/ON{slash}OFF") (class "Default")
      (node (ref "R2") (pin "2") (pinfunction "2_2") (pintype "passive"))
      (node (ref "U1") (pin "59") (pinfunction "PB7_59") (pintype "bidirectional"))
    )
    (net (code "85") (name "/OSC_IN") (class "Default")
      (node (ref "C19") (pin "2") (pinfunction "2_2") (pintype "passive"))
      (node (ref "R25") (pin "2") (pinfunction "2_2") (pintype "passive"))
      (node (ref "U1") (pin "5") (pinfunction "OSC_IN/PD0_5") (pintype "input"))
      (node (ref "Y1") (pin "2") (pinfunction "OSC2_2") (pintype "passive"))
    )
    (net (code "86") (name "/OSC_OUT") (class "Default")
      (node (ref "C20") (pin "2") (pinfunction "2_2") (pintype "passive"))
      (node (ref "R25") (pin "1") (pinfunction "1_1") (pintype "passive"))
      (node (ref "U1") (pin "6") (pinfunction "OSC_OUT/PD1_6") (pintype "output"))
      (node (ref "Y1") (pin "1") (pinfunction "OSC1_1") (pintype "passive"))
    )
    (net (code "87") (name "/RESET") (class "Default")
      (node (ref "C18") (pin "1") (pinfunction "1_1") (pintype "passive"))
      (node (ref "R20") (pin "1") (pinfunction "1_1") (pintype "passive"))
      (node (ref "RST") (pin "1") (pinfunction "1_1") (pintype "passive"))
      (node (ref "U1") (pin "7") (pinfunction "NRST_7") (pintype "bidirectional"))
    )
    (net (code "88") (name "/SCL") (class "Default")
      (node (ref "R30") (pin "1") (pinfunction "1_1") (pintype "passive"))
      (node (ref "U1") (pin "37") (pinfunction "PC6_37") (pintype "bidirectional"))
      (node (ref "U6") (pin "16") (pinfunction "SCL_16") (pintype "passive"))
      (node (ref "U7") (pin "3") (pinfunction "SCL_3") (pintype "passive"))
    )
    (net (code "89") (name "/SDA") (class "Default")
      (node (ref "R29") (pin "1") (pinfunction "1_1") (pintype "passive"))
      (node (ref "U1") (pin "38") (pinfunction "PC7_38") (pintype "bidirectional"))
      (node (ref "U6") (pin "15") (pinfunction "SDA_15") (pintype "passive"))
      (node (ref "U7") (pin "4") (pinfunction "SDA_4") (pintype "passive"))
    )
    (net (code "90") (name "/SWCLK") (class "Default")
      (node (ref "P1") (pin "4") (pinfunction "4_4") (pintype "passive"))
      (node (ref "U1") (pin "49") (pinfunction "PA14/JTCK/SWCLK_49") (pintype "bidirectional"))
    )
    (net (code "91") (name "/SWDIO") (class "Default")
      (node (ref "P1") (pin "3") (pinfunction "3_3") (pintype "passive"))
      (node (ref "U1") (pin "46") (pinfunction "PA13/JTMS/SWDIO_46") (pintype "bidirectional"))
    )
    (net (code "92") (name "/USB_D+") (class "Default")
      (node (ref "J1") (pin "3") (pinfunction "D+_3") (pintype "passive"))
      (node (ref "R22") (pin "1") (pinfunction "1_1") (pintype "passive"))
      (node (ref "R24") (pin "1") (pinfunction "1_1") (pintype "passive"))
    )
    (net (code "93") (name "/USB_D-") (class "Default")
      (node (ref "J1") (pin "2") (pinfunction "D-_2") (pintype "passive"))
      (node (ref "R21") (pin "1") (pinfunction "1_1") (pintype "passive"))
    )
    (net (code "94") (name "GND") (class "Default")
      (node (ref "BT") (pin "2") (pintype "passive"))
      (node (ref "C1") (pin "2") (pinfunction "2_2") (pintype "passive"))
      (node (ref "C10") (pin "2") (pinfunction "2_2") (pintype "passive"))
      (node (ref "C11") (pin "2") (pinfunction "2_2") (pintype "passive"))
      (node (ref "C12") (pin "1") (pinfunction "1_1") (pintype "passive"))
      (node (ref "C13") (pin "1") (pinfunction "1_1") (pintype "passive"))
      (node (ref "C14") (pin "1") (pinfunction "1_1") (pintype "passive"))
      (node (ref "C15") (pin "1") (pinfunction "1_1") (pintype "passive"))
      (node (ref "C16") (pin "1") (pinfunction "1_1") (pintype "passive"))
      (node (ref "C17") (pin "2") (pinfunction "2_2") (pintype "passive"))
      (node (ref "C18") (pin "2") (pinfunction "2_2") (pintype "passive"))
      (node (ref "C19") (pin "1") (pinfunction "1_1") (pintype "passive"))
      (node (ref "C20") (pin "1") (pinfunction "1_1") (pintype "passive"))
      (node (ref "C23") (pin "2") (pinfunction "2_2") (pintype "passive"))
      (node (ref "C24") (pin "2") (pinfunction "2_2") (pintype "passive"))
      (node (ref "C25") (pin "2") (pinfunction "2_2") (pintype "passive"))
      (node (ref "C26") (pin "2") (pinfunction "2_2") (pintype "passive"))
      (node (ref "C27") (pin "2") (pinfunction "2_2") (pintype "passive"))
      (node (ref "C28") (pin "2") (pinfunction "2_2") (pintype "passive"))
      (node (ref "C29") (pin "2") (pinfunction "2_2") (pintype "passive"))
      (node (ref "C7") (pin "2") (pinfunction "2_2") (pintype "passive"))
      (node (ref "C8") (pin "2") (pinfunction "2_2") (pintype "passive"))
      (node (ref "C9") (pin "2") (pinfunction "2_2") (pintype "passive"))
      (node (ref "J1") (pin "5") (pinfunction "VSS_5") (pintype "passive"))
      (node (ref "KEY0") (pin "2") (pinfunction "2_2") (pintype "passive"))
      (node (ref "KEY1") (pin "2") (pinfunction "2_2") (pintype "passive"))
      (node (ref "KEY2") (pin "2") (pinfunction "2_2") (pintype "passive"))
      (node (ref "P1") (pin "2") (pinfunction "2_2") (pintype "passive"))
      (node (ref "Q5") (pin "2") (pinfunction "E_2") (pintype "passive"))
      (node (ref "Q6") (pin "2") (pinfunction "E_2") (pintype "passive"))
      (node (ref "R23") (pin "1") (pinfunction "1_1") (pintype "passive"))
      (node (ref "R26") (pin "2") (pinfunction "2_2") (pintype "passive"))
      (node (ref "RGB1") (pin "3") (pinfunction "VSS_3") (pintype "passive"))
      (node (ref "RGB2") (pin "3") (pinfunction "VSS_3") (pintype "passive"))
      (node (ref "RGB3") (pin "3") (pinfunction "VSS_3") (pintype "passive"))
      (node (ref "RGB4") (pin "3") (pinfunction "VSS_3") (pintype "passive"))
      (node (ref "RGB5") (pin "3") (pinfunction "VSS_3") (pintype "passive"))
      (node (ref "RGB6") (pin "3") (pinfunction "VSS_3") (pintype "passive"))
      (node (ref "RST") (pin "2") (pinfunction "2_2") (pintype "passive"))
      (node (ref "U1") (pin "12") (pinfunction "VSSA_12") (pintype "power_in"))
      (node (ref "U1") (pin "18") (pinfunction "VSS_4_18") (pintype "power_in"))
      (node (ref "U1") (pin "31") (pinfunction "VSS_1_31") (pintype "power_in"))
      (node (ref "U1") (pin "47") (pinfunction "VSS_2_47") (pintype "power_in"))
      (node (ref "U1") (pin "63") (pinfunction "VSS_3_63") (pintype "power_in"))
      (node (ref "U3") (pin "1") (pinfunction "GND_1") (pintype "passive"))
      (node (ref "U4") (pin "2") (pinfunction "GND_2") (pintype "passive"))
      (node (ref "U5") (pin "34") (pinfunction "GND_34") (pintype "passive"))
      (node (ref "U6") (pin "10") (pinfunction "N.C._10") (pintype "passive"))
      (node (ref "U6") (pin "11") (pinfunction "N.C._11") (pintype "passive"))
      (node (ref "U6") (pin "12") (pinfunction "N.C._12") (pintype "passive"))
      (node (ref "U6") (pin "13") (pinfunction "GND_13") (pintype "passive"))
      (node (ref "U6") (pin "5") (pinfunction "N.C._5") (pintype "passive"))
      (node (ref "U6") (pin "6") (pinfunction "N.C._6") (pintype "passive"))
      (node (ref "U6") (pin "7") (pinfunction "N.C._7") (pintype "passive"))
      (node (ref "U6") (pin "8") (pinfunction "N.C._8") (pintype "passive"))
      (node (ref "U6") (pin "9") (pinfunction "N.C._9") (pintype "passive"))
      (node (ref "U7") (pin "2") (pinfunction "GND_2") (pintype "passive"))
      (node (ref "U8") (pin "13") (pinfunction "GND_13") (pintype "passive"))
    )
    (net (code "95") (name "GNDH") (class "Default")
      (node (ref "D2") (pin "1") (pinfunction "A_1") (pintype "passive"))
      (node (ref "Q1") (pin "2") (pinfunction "E_2") (pintype "passive"))
      (node (ref "Q2") (pin "2") (pinfunction "E_2") (pintype "passive"))
      (node (ref "Q3") (pin "2") (pinfunction "E_2") (pintype "passive"))
      (node (ref "Q4") (pin "2") (pinfunction "E_2") (pintype "passive"))
      (node (ref "U4") (pin "3") (pinfunction "GNDH_3") (pintype "passive"))
    )
    (net (code "96") (name "Net-(B-1)") (class "Default")
      (node (ref "B") (pin "2") (pinfunction "1_2") (pintype "passive"))
      (node (ref "Q6") (pin "3") (pinfunction "C_3") (pintype "passive"))
    )
    (net (code "97") (name "Net-(D2-K)") (class "Default")
      (node (ref "D2") (pin "2") (pinfunction "K_2") (pintype "passive"))
      (node (ref "R31") (pin "2") (pinfunction "2_2") (pintype "passive"))
      (node (ref "U5") (pin "40") (pinfunction "VPP_40") (pintype "passive"))
    )
    (net (code "98") (name "Net-(D3-K)") (class "Default")
      (node (ref "D3") (pin "2") (pinfunction "K_2") (pintype "passive"))
      (node (ref "R32") (pin "2") (pinfunction "2_2") (pintype "passive"))
    )
    (net (code "99") (name "Net-(DS1-Pad2)") (class "Default")
      (node (ref "DS1") (pin "2") (pintype "passive"))
      (node (ref "R12") (pin "2") (pinfunction "2_2") (pintype "passive"))
    )
    (net (code "100") (name "Net-(DS2-Pad2)") (class "Default")
      (node (ref "DS2") (pin "2") (pintype "passive"))
      (node (ref "R13") (pin "2") (pinfunction "2_2") (pintype "passive"))
    )
    (net (code "101") (name "Net-(DS3-Pad2)") (class "Default")
      (node (ref "DS3") (pin "2") (pintype "passive"))
      (node (ref "R14") (pin "1") (pinfunction "1_1") (pintype "passive"))
    )
    (net (code "102") (name "Net-(DS4-Pad2)") (class "Default")
      (node (ref "DS4") (pin "2") (pintype "passive"))
      (node (ref "R15") (pin "2") (pinfunction "2_2") (pintype "passive"))
    )
    (net (code "103") (name "Net-(J1-VCC)") (class "Default")
      (node (ref "F1") (pin "1") (pinfunction "1_1") (pintype "passive"))
      (node (ref "J1") (pin "1") (pinfunction "VCC_1") (pintype "passive"))
    )
    (net (code "104") (name "Net-(N1-VCC)") (class "Default")
      (node (ref "N1") (pin "1") (pinfunction "VCC_1") (pintype "passive"))
      (node (ref "R6") (pin "1") (pinfunction "1_1") (pintype "passive"))
    )
    (net (code "105") (name "Net-(N2-VCC)") (class "Default")
      (node (ref "N2") (pin "1") (pinfunction "VCC_1") (pintype "passive"))
      (node (ref "R7") (pin "1") (pinfunction "1_1") (pintype "passive"))
    )
    (net (code "106") (name "Net-(N3-VCC)") (class "Default")
      (node (ref "N3") (pin "1") (pinfunction "VCC_1") (pintype "passive"))
      (node (ref "R8") (pin "1") (pinfunction "1_1") (pintype "passive"))
    )
    (net (code "107") (name "Net-(N4-VCC)") (class "Default")
      (node (ref "N4") (pin "1") (pinfunction "VCC_1") (pintype "passive"))
      (node (ref "R9") (pin "1") (pinfunction "1_1") (pintype "passive"))
    )
    (net (code "108") (name "Net-(N5-VCC)") (class "Default")
      (node (ref "N5") (pin "1") (pinfunction "VCC_1") (pintype "passive"))
      (node (ref "R10") (pin "1") (pinfunction "1_1") (pintype "passive"))
    )
    (net (code "109") (name "Net-(N6-VCC)") (class "Default")
      (node (ref "N6") (pin "1") (pinfunction "VCC_1") (pintype "passive"))
      (node (ref "R11") (pin "1") (pinfunction "1_1") (pintype "passive"))
    )
    (net (code "110") (name "Net-(Q1-B)") (class "Default")
      (node (ref "Q1") (pin "1") (pinfunction "B_1") (pintype "passive"))
      (node (ref "R16") (pin "2") (pinfunction "2_2") (pintype "passive"))
    )
    (net (code "111") (name "Net-(Q1-C)") (class "Default")
      (node (ref "DS1") (pin "1") (pintype "passive"))
      (node (ref "Q1") (pin "3") (pinfunction "C_3") (pintype "passive"))
    )
    (net (code "112") (name "Net-(Q2-B)") (class "Default")
      (node (ref "Q2") (pin "1") (pinfunction "B_1") (pintype "passive"))
      (node (ref "R17") (pin "2") (pinfunction "2_2") (pintype "passive"))
    )
    (net (code "113") (name "Net-(Q2-C)") (class "Default")
      (node (ref "DS2") (pin "1") (pintype "passive"))
      (node (ref "Q2") (pin "3") (pinfunction "C_3") (pintype "passive"))
    )
    (net (code "114") (name "Net-(Q3-B)") (class "Default")
      (node (ref "Q3") (pin "1") (pinfunction "B_1") (pintype "passive"))
      (node (ref "R18") (pin "2") (pinfunction "2_2") (pintype "passive"))
    )
    (net (code "115") (name "Net-(Q3-C)") (class "Default")
      (node (ref "DS3") (pin "1") (pintype "passive"))
      (node (ref "Q3") (pin "3") (pinfunction "C_3") (pintype "passive"))
    )
    (net (code "116") (name "Net-(Q4-B)") (class "Default")
      (node (ref "Q4") (pin "1") (pinfunction "B_1") (pintype "passive"))
      (node (ref "R19") (pin "2") (pinfunction "2_2") (pintype "passive"))
    )
    (net (code "117") (name "Net-(Q4-C)") (class "Default")
      (node (ref "DS4") (pin "1") (pintype "passive"))
      (node (ref "Q4") (pin "3") (pinfunction "C_3") (pintype "passive"))
    )
    (net (code "118") (name "Net-(Q5-B)") (class "Default")
      (node (ref "Q5") (pin "1") (pinfunction "B_1") (pintype "passive"))
      (node (ref "R2") (pin "1") (pinfunction "1_1") (pintype "passive"))
    )
    (net (code "119") (name "Net-(Q5-C)") (class "Default")
      (node (ref "Q5") (pin "3") (pinfunction "C_3") (pintype "passive"))
      (node (ref "U9") (pin "2") (pinfunction "2_2") (pintype "passive"))
    )
    (net (code "120") (name "Net-(Q6-B)") (class "Default")
      (node (ref "Q6") (pin "1") (pinfunction "B_1") (pintype "passive"))
      (node (ref "R27") (pin "2") (pinfunction "2_2") (pintype "passive"))
    )
    (net (code "121") (name "Net-(R1-Pad2)") (class "Default")
      (node (ref "R1") (pin "2") (pinfunction "2_2") (pintype "passive"))
      (node (ref "U9") (pin "1") (pinfunction "1_1") (pintype "passive"))
    )
    (net (code "122") (name "Net-(RGB1-DO)") (class "Default")
      (node (ref "RGB1") (pin "2") (pinfunction "DO_2") (pintype "passive"))
      (node (ref "RGB2") (pin "4") (pinfunction "DI_4") (pintype "passive"))
    )
    (net (code "123") (name "Net-(RGB2-DO)") (class "Default")
      (node (ref "RGB2") (pin "2") (pinfunction "DO_2") (pintype "passive"))
      (node (ref "RGB3") (pin "4") (pinfunction "DI_4") (pintype "passive"))
    )
    (net (code "124") (name "Net-(RGB3-DO)") (class "Default")
      (node (ref "RGB3") (pin "2") (pinfunction "DO_2") (pintype "passive"))
      (node (ref "RGB4") (pin "4") (pinfunction "DI_4") (pintype "passive"))
    )
    (net (code "125") (name "Net-(RGB4-DO)") (class "Default")
      (node (ref "RGB4") (pin "2") (pinfunction "DO_2") (pintype "passive"))
      (node (ref "RGB5") (pin "4") (pinfunction "DI_4") (pintype "passive"))
    )
    (net (code "126") (name "Net-(RGB5-DO)") (class "Default")
      (node (ref "RGB5") (pin "2") (pinfunction "DO_2") (pintype "passive"))
      (node (ref "RGB6") (pin "4") (pinfunction "DI_4") (pintype "passive"))
    )
    (net (code "127") (name "Net-(U1-BOOT0)") (class "Default")
      (node (ref "R23") (pin "2") (pinfunction "2_2") (pintype "passive"))
      (node (ref "U1") (pin "60") (pinfunction "BOOT0_60") (pintype "input"))
    )
    (net (code "128") (name "Net-(U1-PA11)") (class "Default")
      (node (ref "R21") (pin "2") (pinfunction "2_2") (pintype "passive"))
      (node (ref "U1") (pin "44") (pinfunction "PA11_44") (pintype "bidirectional"))
    )
    (net (code "129") (name "Net-(U1-PA12)") (class "Default")
      (node (ref "R22") (pin "2") (pinfunction "2_2") (pintype "passive"))
      (node (ref "U1") (pin "45") (pinfunction "PA12_45") (pintype "bidirectional"))
    )
    (net (code "130") (name "Net-(U1-PB2{slash}BOOT1)") (class "Default")
      (node (ref "R26") (pin "1") (pinfunction "1_1") (pintype "passive"))
      (node (ref "U1") (pin "28") (pinfunction "PB2/BOOT1_28") (pintype "bidirectional"))
    )
    (net (code "131") (name "Net-(U4-+5V)") (class "Default")
      (node (ref "U4") (pin "1") (pinfunction "+5V_1") (pintype "passive"))
      (node (ref "U9") (pin "3") (pinfunction "3_3") (pintype "passive"))
    )
    (net (code "132") (name "Net-(U6-VBAT)") (class "Default")
      (node (ref "BT") (pin "1") (pintype "passive"))
      (node (ref "U6") (pin "14") (pinfunction "VBAT_14") (pintype "passive"))
    )
    (net (code "133") (name "VCC3.3") (class "Default")
      (node (ref "B") (pin "1") (pinfunction "0_1") (pintype "passive"))
      (node (ref "C10") (pin "1") (pinfunction "1_1") (pintype "passive"))
      (node (ref "C12") (pin "2") (pinfunction "2_2") (pintype "passive"))
      (node (ref "C13") (pin "2") (pinfunction "2_2") (pintype "passive"))
      (node (ref "C14") (pin "2") (pinfunction "2_2") (pintype "passive"))
      (node (ref "C15") (pin "2") (pinfunction "2_2") (pintype "passive"))
      (node (ref "C16") (pin "2") (pinfunction "2_2") (pintype "passive"))
      (node (ref "C17") (pin "1") (pinfunction "1_1") (pintype "passive"))
      (node (ref "C23") (pin "1") (pinfunction "1_1") (pintype "passive"))
      (node (ref "C9") (pin "1") (pinfunction "1_1") (pintype "passive"))
      (node (ref "D3") (pin "1") (pinfunction "A_1") (pintype "passive"))
      (node (ref "P1") (pin "1") (pinfunction "1_1") (pintype "passive"))
      (node (ref "R20") (pin "2") (pinfunction "2_2") (pintype "passive"))
      (node (ref "R24") (pin "2") (pinfunction "2_2") (pintype "passive"))
      (node (ref "R28") (pin "2") (pinfunction "2_2") (pintype "passive"))
      (node (ref "R29") (pin "2") (pinfunction "2_2") (pintype "passive"))
      (node (ref "R30") (pin "2") (pinfunction "2_2") (pintype "passive"))
      (node (ref "U1") (pin "1") (pinfunction "VBAT_1") (pintype "power_in"))
      (node (ref "U1") (pin "13") (pinfunction "VDDA_13") (pintype "power_in"))
      (node (ref "U1") (pin "19") (pinfunction "VDD_4_19") (pintype "power_in"))
      (node (ref "U1") (pin "32") (pinfunction "VDD_1_32") (pintype "power_in"))
      (node (ref "U1") (pin "48") (pinfunction "VDD_2_48") (pintype "power_in"))
      (node (ref "U1") (pin "64") (pinfunction "VDD_3_64") (pintype "power_in"))
      (node (ref "U3") (pin "2") (pinfunction "OUT_2") (pintype "passive"))
      (node (ref "U6") (pin "2") (pinfunction "VCC_2") (pintype "passive"))
      (node (ref "U7") (pin "1") (pinfunction "VIN_1") (pintype "passive"))
      (node (ref "U8") (pin "12") (pinfunction "3.3V_12") (pintype "passive"))
    )
    (net (code "134") (name "VCC5") (class "Default")
      (node (ref "C1") (pin "1") (pinfunction "1_1") (pintype "passive"))
      (node (ref "C11") (pin "1") (pinfunction "1_1") (pintype "passive"))
      (node (ref "C24") (pin "1") (pinfunction "1_1") (pintype "passive"))
      (node (ref "C25") (pin "1") (pinfunction "1_1") (pintype "passive"))
      (node (ref "C26") (pin "1") (pinfunction "1_1") (pintype "passive"))
      (node (ref "C27") (pin "1") (pinfunction "1_1") (pintype "passive"))
      (node (ref "C28") (pin "1") (pinfunction "1_1") (pintype "passive"))
      (node (ref "C29") (pin "1") (pinfunction "1_1") (pintype "passive"))
      (node (ref "C7") (pin "1") (pinfunction "1_1") (pintype "passive"))
      (node (ref "C8") (pin "1") (pinfunction "1_1") (pintype "passive"))
      (node (ref "FB1") (pin "2") (pinfunction "2_2") (pintype "passive"))
      (node (ref "R1") (pin "1") (pinfunction "1_1") (pintype "passive"))
      (node (ref "R33") (pin "2") (pinfunction "2_2") (pintype "passive"))
      (node (ref "R34") (pin "2") (pinfunction "2_2") (pintype "passive"))
      (node (ref "R35") (pin "2") (pinfunction "2_2") (pintype "passive"))
      (node (ref "R36") (pin "2") (pinfunction "2_2") (pintype "passive"))
      (node (ref "R37") (pin "2") (pinfunction "2_2") (pintype "passive"))
      (node (ref "R38") (pin "2") (pinfunction "2_2") (pintype "passive"))
      (node (ref "R39") (pin "2") (pinfunction "2_2") (pintype "passive"))
      (node (ref "RGB1") (pin "1") (pinfunction "VDD_1") (pintype "passive"))
      (node (ref "RGB2") (pin "1") (pinfunction "VDD_1") (pintype "passive"))
      (node (ref "RGB3") (pin "1") (pinfunction "VDD_1") (pintype "passive"))
      (node (ref "RGB4") (pin "1") (pinfunction "VDD_1") (pintype "passive"))
      (node (ref "RGB5") (pin "1") (pinfunction "VDD_1") (pintype "passive"))
      (node (ref "RGB6") (pin "1") (pinfunction "VDD_1") (pintype "passive"))
      (node (ref "U3") (pin "3") (pinfunction "IN_3") (pintype "passive"))
      (node (ref "U5") (pin "31") (pinfunction "~{BL}_31") (pintype "passive"))
      (node (ref "U5") (pin "32") (pinfunction "VDD_32") (pintype "passive"))
      (node (ref "U5") (pin "33") (pinfunction "DIR_33") (pintype "passive"))
    )
    (net (code "135") (name "VCCH") (class "Default")
      (node (ref "R10") (pin "2") (pinfunction "2_2") (pintype "passive"))
      (node (ref "R11") (pin "2") (pinfunction "2_2") (pintype "passive"))
      (node (ref "R12") (pin "1") (pinfunction "1_1") (pintype "passive"))
      (node (ref "R13") (pin "1") (pinfunction "1_1") (pintype "passive"))
      (node (ref "R14") (pin "2") (pinfunction "2_2") (pintype "passive"))
      (node (ref "R15") (pin "1") (pinfunction "1_1") (pintype "passive"))
      (node (ref "R31") (pin "1") (pinfunction "1_1") (pintype "passive"))
      (node (ref "R6") (pin "2") (pinfunction "2_2") (pintype "passive"))
      (node (ref "R7") (pin "2") (pinfunction "2_2") (pintype "passive"))
      (node (ref "R8") (pin "2") (pinfunction "2_2") (pintype "passive"))
      (node (ref "R9") (pin "2") (pinfunction "2_2") (pintype "passive"))
      (node (ref "U4") (pin "4") (pinfunction "VCCH_4") (pintype "passive"))
    )
    (net (code "136") (name "unconnected-(J1-ID-Pad4)") (class "Default")
      (node (ref "J1") (pin "4") (pinfunction "ID_4") (pintype "passive+no_connect"))
    )
    (net (code "137") (name "unconnected-(N1-LP-Pad2)") (class "Default")
      (node (ref "N1") (pin "2") (pinfunction "LP_2") (pintype "passive"))
    )
    (net (code "138") (name "unconnected-(N1-RP-Pad13)") (class "Default")
      (node (ref "N1") (pin "13") (pinfunction "RP_13") (pintype "passive"))
    )
    (net (code "139") (name "unconnected-(N2-LP-Pad2)") (class "Default")
      (node (ref "N2") (pin "2") (pinfunction "LP_2") (pintype "passive"))
    )
    (net (code "140") (name "unconnected-(N2-RP-Pad13)") (class "Default")
      (node (ref "N2") (pin "13") (pinfunction "RP_13") (pintype "passive"))
    )
    (net (code "141") (name "unconnected-(N3-LP-Pad2)") (class "Default")
      (node (ref "N3") (pin "2") (pinfunction "LP_2") (pintype "passive"))
    )
    (net (code "142") (name "unconnected-(N3-RP-Pad13)") (class "Default")
      (node (ref "N3") (pin "13") (pinfunction "RP_13") (pintype "passive"))
    )
    (net (code "143") (name "unconnected-(N4-LP-Pad2)") (class "Default")
      (node (ref "N4") (pin "2") (pinfunction "LP_2") (pintype "passive"))
    )
    (net (code "144") (name "unconnected-(N4-RP-Pad13)") (class "Default")
      (node (ref "N4") (pin "13") (pinfunction "RP_13") (pintype "passive"))
    )
    (net (code "145") (name "unconnected-(N5-LP-Pad2)") (class "Default")
      (node (ref "N5") (pin "2") (pinfunction "LP_2") (pintype "passive"))
    )
    (net (code "146") (name "unconnected-(N5-RP-Pad13)") (class "Default")
      (node (ref "N5") (pin "13") (pinfunction "RP_13") (pintype "passive"))
    )
    (net (code "147") (name "unconnected-(N6-LP-Pad2)") (class "Default")
      (node (ref "N6") (pin "2") (pinfunction "LP_2") (pintype "passive"))
    )
    (net (code "148") (name "unconnected-(N6-RP-Pad13)") (class "Default")
      (node (ref "N6") (pin "13") (pinfunction "RP_13") (pintype "passive"))
    )
    (net (code "149") (name "unconnected-(RGB6-DO-Pad2)") (class "Default")
      (node (ref "RGB6") (pin "2") (pinfunction "DO_2") (pintype "passive"))
    )
    (net (code "150") (name "unconnected-(U1-PA2-Pad16)") (class "Default")
      (node (ref "U1") (pin "16") (pinfunction "PA2_16") (pintype "bidirectional"))
    )
    (net (code "151") (name "unconnected-(U1-PA3-Pad17)") (class "Default")
      (node (ref "U1") (pin "17") (pinfunction "PA3_17") (pintype "bidirectional"))
    )
    (net (code "152") (name "unconnected-(U1-PA7-Pad23)") (class "Default")
      (node (ref "U1") (pin "23") (pinfunction "PA7_23") (pintype "bidirectional"))
    )
    (net (code "153") (name "unconnected-(U1-PA8-Pad41)") (class "Default")
      (node (ref "U1") (pin "41") (pinfunction "PA8_41") (pintype "bidirectional"))
    )
    (net (code "154") (name "unconnected-(U1-PA15{slash}JTDI-Pad50)") (class "Default")
      (node (ref "U1") (pin "50") (pinfunction "PA15/JTDI_50") (pintype "bidirectional"))
    )
    (net (code "155") (name "unconnected-(U1-PB0-Pad26)") (class "Default")
      (node (ref "U1") (pin "26") (pinfunction "PB0_26") (pintype "bidirectional"))
    )
    (net (code "156") (name "unconnected-(U1-PB1-Pad27)") (class "Default")
      (node (ref "U1") (pin "27") (pinfunction "PB1_27") (pintype "bidirectional"))
    )
    (net (code "157") (name "unconnected-(U1-PB3{slash}JTDO-Pad55)") (class "Default")
      (node (ref "U1") (pin "55") (pinfunction "PB3/JTDO_55") (pintype "bidirectional"))
    )
    (net (code "158") (name "unconnected-(U1-PB4{slash}JNTRST-Pad56)") (class "Default")
      (node (ref "U1") (pin "56") (pinfunction "PB4/JNTRST_56") (pintype "bidirectional"))
    )
    (net (code "159") (name "unconnected-(U1-PB6-Pad58)") (class "Default")
      (node (ref "U1") (pin "58") (pinfunction "PB6_58") (pintype "bidirectional"))
    )
    (net (code "160") (name "unconnected-(U1-PB8-Pad61)") (class "Default")
      (node (ref "U1") (pin "61") (pinfunction "PB8_61") (pintype "bidirectional"))
    )
    (net (code "161") (name "unconnected-(U1-PB9-Pad62)") (class "Default")
      (node (ref "U1") (pin "62") (pinfunction "PB9_62") (pintype "bidirectional"))
    )
    (net (code "162") (name "unconnected-(U1-PB10-Pad29)") (class "Default")
      (node (ref "U1") (pin "29") (pinfunction "PB10_29") (pintype "bidirectional"))
    )
    (net (code "163") (name "unconnected-(U1-PB11-Pad30)") (class "Default")
      (node (ref "U1") (pin "30") (pinfunction "PB11_30") (pintype "bidirectional"))
    )
    (net (code "164") (name "unconnected-(U1-PC4-Pad24)") (class "Default")
      (node (ref "U1") (pin "24") (pinfunction "PC4_24") (pintype "bidirectional"))
    )
    (net (code "165") (name "unconnected-(U1-PC5-Pad25)") (class "Default")
      (node (ref "U1") (pin "25") (pinfunction "PC5_25") (pintype "bidirectional"))
    )
    (net (code "166") (name "unconnected-(U1-PC14-OSC32_IN-Pad3)") (class "Default")
      (node (ref "U1") (pin "3") (pinfunction "PC14-OSC32_IN_3") (pintype "bidirectional"))
    )
    (net (code "167") (name "unconnected-(U1-PC15-OSC32_OUT-Pad4)") (class "Default")
      (node (ref "U1") (pin "4") (pinfunction "PC15-OSC32_OUT_4") (pintype "bidirectional"))
    )
    (net (code "168") (name "unconnected-(U1-PD2-Pad54)") (class "Default")
      (node (ref "U1") (pin "54") (pinfunction "PD2_54") (pintype "bidirectional"))
    )
    (net (code "169") (name "unconnected-(U5-DOUT1{slash}DIN4(B)-Pad39)") (class "Default")
      (node (ref "U5") (pin "39") (pinfunction "DOUT1/DIN4(B)_39") (pintype "passive"))
    )
    (net (code "170") (name "unconnected-(U5-DOUT2{slash}DIN3(B)-Pad38)") (class "Default")
      (node (ref "U5") (pin "38") (pinfunction "DOUT2/DIN3(B)_38") (pintype "passive"))
    )
    (net (code "171") (name "unconnected-(U5-DOUT3{slash}DIN2(B)-Pad37)") (class "Default")
      (node (ref "U5") (pin "37") (pinfunction "DOUT3/DIN2(B)_37") (pintype "passive"))
    )
    (net (code "172") (name "unconnected-(U5-DOUT4{slash}DIN1(B)-Pad36)") (class "Default")
      (node (ref "U5") (pin "36") (pinfunction "DOUT4/DIN1(B)_36") (pintype "passive"))
    )
    (net (code "173") (name "unconnected-(U5-HVOUT61{slash}4-Pad44)") (class "Default")
      (node (ref "U5") (pin "44") (pinfunction "HVOUT61/4_44") (pintype "passive"))
    )
    (net (code "174") (name "unconnected-(U5-HVOUT62{slash}3-Pad43)") (class "Default")
      (node (ref "U5") (pin "43") (pinfunction "HVOUT62/3_43") (pintype "passive"))
    )
    (net (code "175") (name "unconnected-(U5-HVOUT63{slash}2-Pad42)") (class "Default")
      (node (ref "U5") (pin "42") (pinfunction "HVOUT63/2_42") (pintype "passive"))
    )
    (net (code "176") (name "unconnected-(U5-HVOUT64{slash}1-Pad41)") (class "Default")
      (node (ref "U5") (pin "41") (pinfunction "HVOUT64/1_41") (pintype "passive"))
    )
    (net (code "177") (name "unconnected-(U6-32kHz-Pad1)") (class "Default")
      (node (ref "U6") (pin "1") (pinfunction "32kHz_1") (pintype "passive"))
    )
    (net (code "178") (name "unconnected-(U6-~{RST}-Pad4)") (class "Default")
      (node (ref "U6") (pin "4") (pinfunction "~{RST}_4") (pintype "passive"))
    )
    (net (code "179") (name "unconnected-(U8-KEY--Pad15)") (class "Default")
      (node (ref "U8") (pin "15") (pinfunction "KEY-_15") (pintype "passive"))
    )
    (net (code "180") (name "unconnected-(U8-LED-Pad16)") (class "Default")
      (node (ref "U8") (pin "16") (pinfunction "LED_16") (pintype "passive"))
    )
    (net (code "181") (name "unconnected-(U8-LEDCON-Pad14)") (class "Default")
      (node (ref "U8") (pin "14") (pinfunction "LEDCON_14") (pintype "passive"))
    )
    (net (code "182") (name "unconnected-(U8-NC-Pad3)") (class "Default")
      (node (ref "U8") (pin "3") (pinfunction "NC_3") (pintype "passive"))
    )
    (net (code "183") (name "unconnected-(U8-NC-Pad4)") (class "Default")
      (node (ref "U8") (pin "4") (pinfunction "NC_4") (pintype "passive"))
    )
    (net (code "184") (name "unconnected-(U8-NC-Pad5)") (class "Default")
      (node (ref "U8") (pin "5") (pinfunction "NC_5") (pintype "passive"))
    )
    (net (code "185") (name "unconnected-(U8-NC-Pad6)") (class "Default")
      (node (ref "U8") (pin "6") (pinfunction "NC_6") (pintype "passive"))
    )
    (net (code "186") (name "unconnected-(U8-NC-Pad7)") (class "Default")
      (node (ref "U8") (pin "7") (pinfunction "NC_7") (pintype "passive"))
    )
    (net (code "187") (name "unconnected-(U8-NC-Pad8)") (class "Default")
      (node (ref "U8") (pin "8") (pinfunction "NC_8") (pintype "passive"))
    )
    (net (code "188") (name "unconnected-(U8-NC-Pad9)") (class "Default")
      (node (ref "U8") (pin "9") (pinfunction "NC_9") (pintype "passive"))
    )
    (net (code "189") (name "unconnected-(U8-NC-Pad10)") (class "Default")
      (node (ref "U8") (pin "10") (pinfunction "NC_10") (pintype "passive"))
    )
    (net (code "190") (name "unconnected-(U8-NC-Pad19)") (class "Default")
      (node (ref "U8") (pin "19") (pinfunction "NC_19") (pintype "passive"))
    )
    (net (code "191") (name "unconnected-(U8-NC-Pad20)") (class "Default")
      (node (ref "U8") (pin "20") (pinfunction "NC_20") (pintype "passive"))
    )
    (net (code "192") (name "unconnected-(U8-NC-Pad21)") (class "Default")
      (node (ref "U8") (pin "21") (pinfunction "NC_21") (pintype "passive"))
    )
    (net (code "193") (name "unconnected-(U8-NC-Pad22)") (class "Default")
      (node (ref "U8") (pin "22") (pinfunction "NC_22") (pintype "passive"))
    )
    (net (code "194") (name "unconnected-(U8-NC-Pad23)") (class "Default")
      (node (ref "U8") (pin "23") (pinfunction "NC_23") (pintype "passive"))
    )
    (net (code "195") (name "unconnected-(U8-NC-Pad24)") (class "Default")
      (node (ref "U8") (pin "24") (pinfunction "NC_24") (pintype "passive"))
    )
    (net (code "196") (name "unconnected-(U8-NC-Pad25)") (class "Default")
      (node (ref "U8") (pin "25") (pinfunction "NC_25") (pintype "passive"))
    )
    (net (code "197") (name "unconnected-(U8-NC-Pad26)") (class "Default")
      (node (ref "U8") (pin "26") (pinfunction "NC_26") (pintype "passive"))
    )
    (net (code "198") (name "unconnected-(U8-~{RST}-Pad11)") (class "Default")
      (node (ref "U8") (pin "11") (pinfunction "~{RST}_11") (pintype "passive"))
    )
  )
)
